# Filtro_8vo_Orden.net
KiCad netlist of a schematic drawn in EAGLE
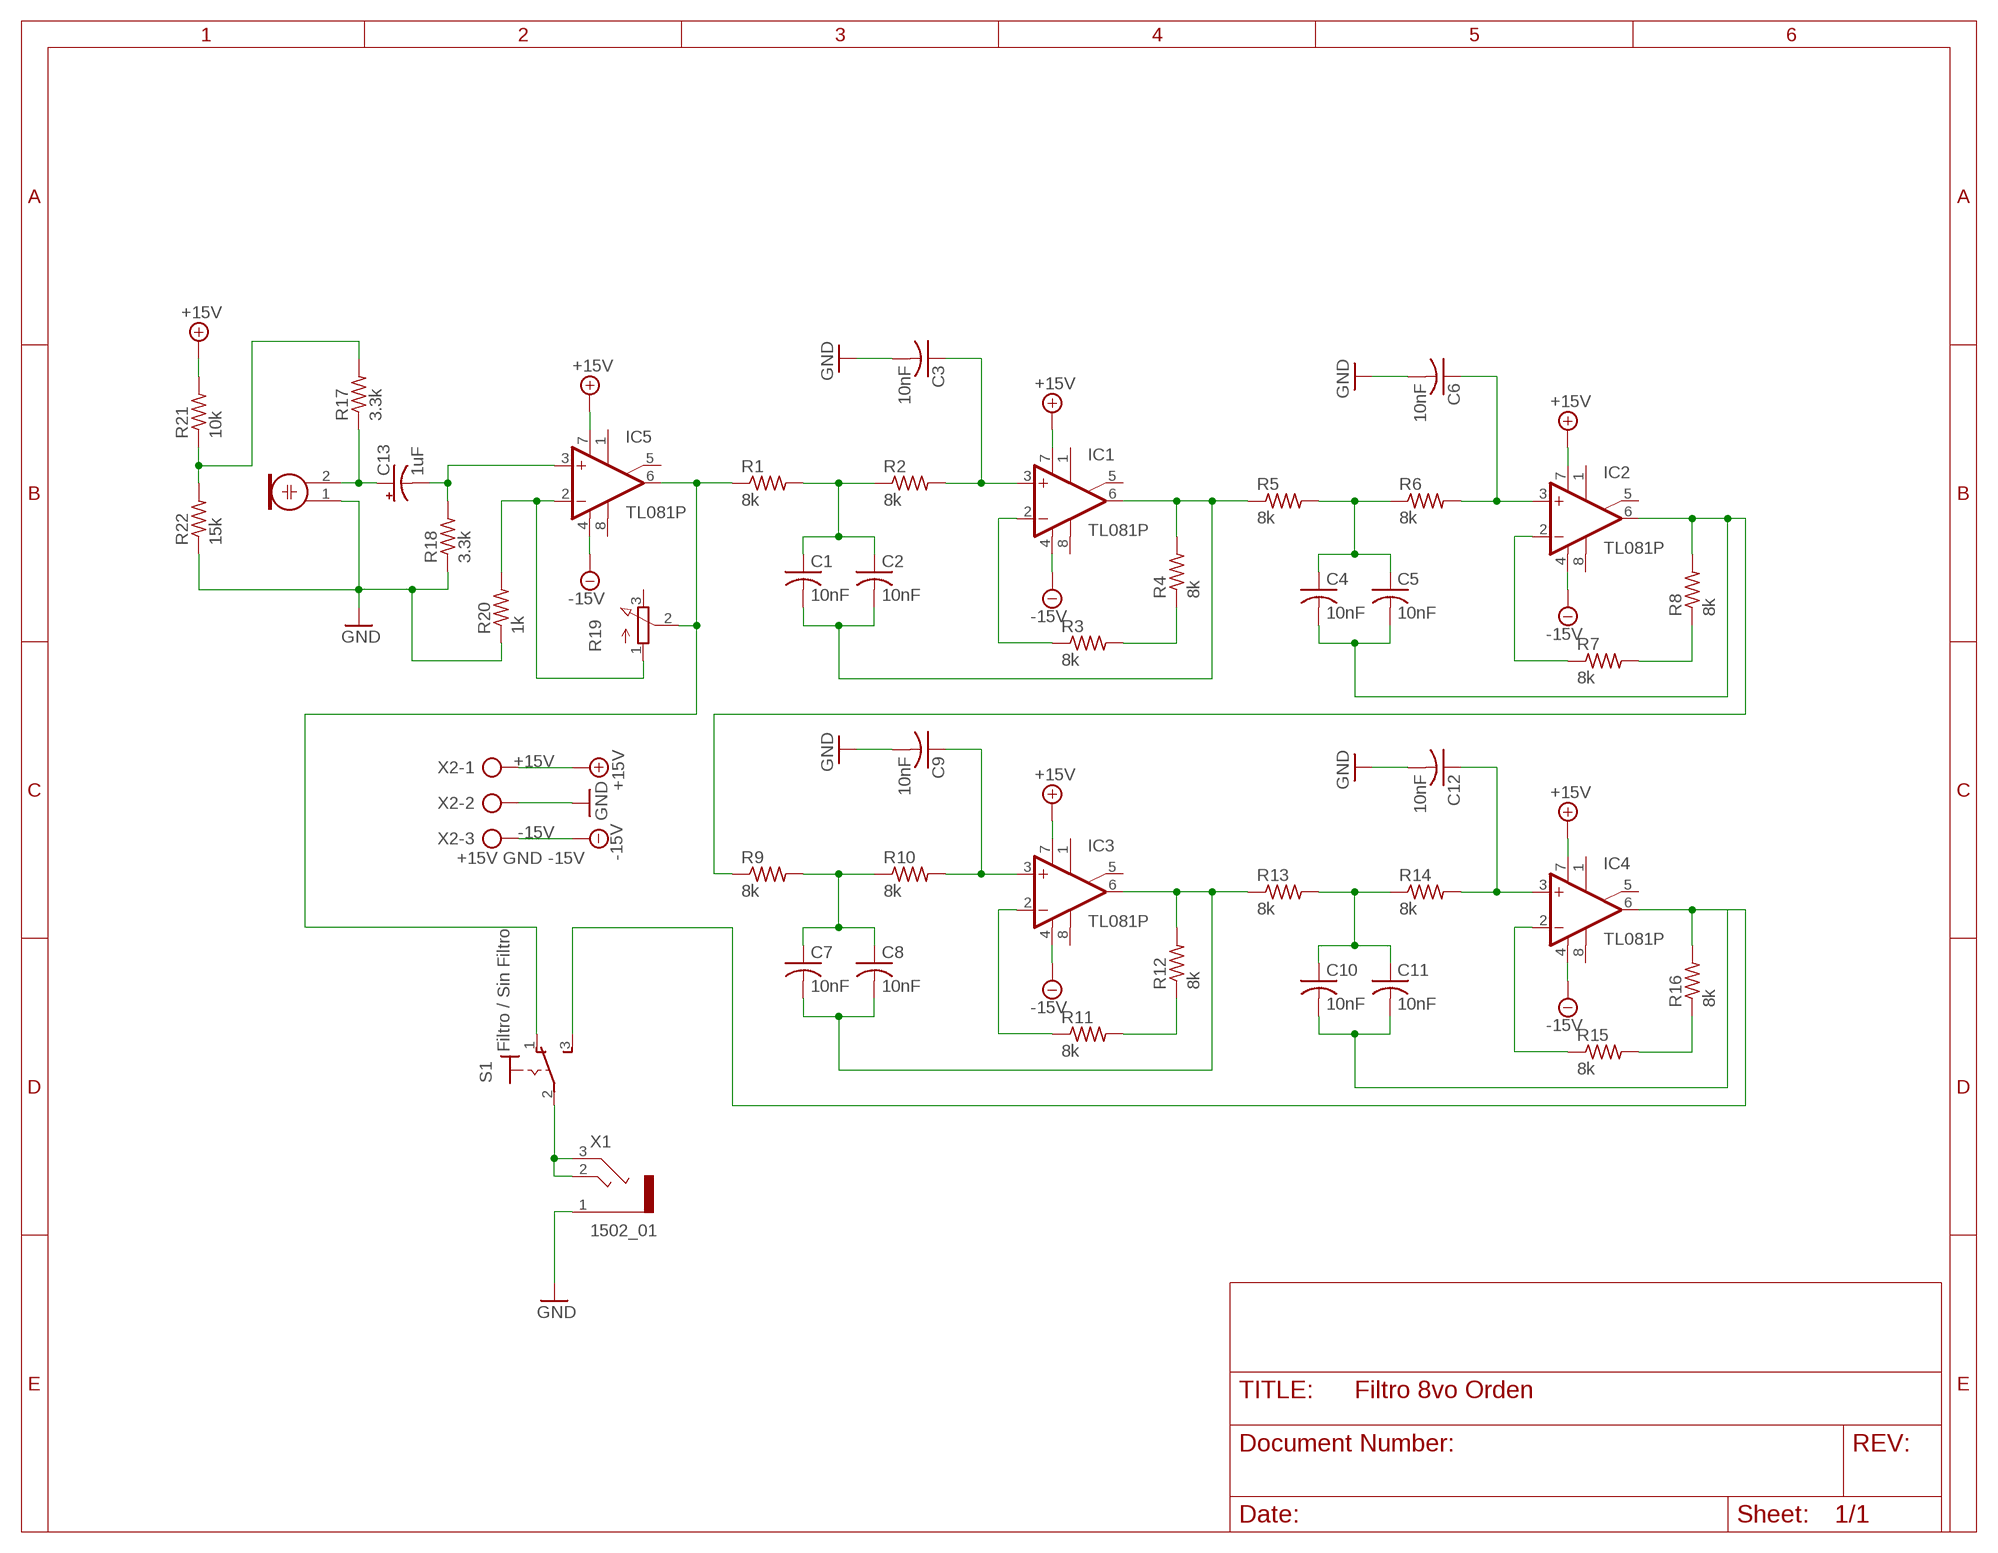
[diagram p0: schematic, sheet 1]

(export (version "E")
  (design (tool "Eeschema 10.0.6"))
  (components
    (comp (ref "C1")
      (value "10nF")
      (footprint "eagle-import:C0805")
      (libsource (lib "eagle-import") (part "C-USC0805"))
    )
    (comp (ref "C2")
      (value "10nF")
      (footprint "eagle-import:C0805")
      (libsource (lib "eagle-import") (part "C-USC0805"))
    )
    (comp (ref "C3")
      (value "10nF")
      (footprint "eagle-import:C0805")
      (libsource (lib "eagle-import") (part "C-USC0805"))
    )
    (comp (ref "C4")
      (value "10nF")
      (footprint "eagle-import:C0805")
      (libsource (lib "eagle-import") (part "C-USC0805"))
    )
    (comp (ref "C5")
      (value "10nF")
      (footprint "eagle-import:C0805")
      (libsource (lib "eagle-import") (part "C-USC0805"))
    )
    (comp (ref "C6")
      (value "10nF")
      (footprint "eagle-import:C0805")
      (libsource (lib "eagle-import") (part "C-USC0805"))
    )
    (comp (ref "C7")
      (value "10nF")
      (footprint "eagle-import:C0805")
      (libsource (lib "eagle-import") (part "C-USC0805"))
    )
    (comp (ref "C8")
      (value "10nF")
      (footprint "eagle-import:C0805")
      (libsource (lib "eagle-import") (part "C-USC0805"))
    )
    (comp (ref "C9")
      (value "10nF")
      (footprint "eagle-import:C0805")
      (libsource (lib "eagle-import") (part "C-USC0805"))
    )
    (comp (ref "C10")
      (value "10nF")
      (footprint "eagle-import:C0805")
      (libsource (lib "eagle-import") (part "C-USC0805"))
    )
    (comp (ref "C11")
      (value "10nF")
      (footprint "eagle-import:C0805")
      (libsource (lib "eagle-import") (part "C-USC0805"))
    )
    (comp (ref "C12")
      (value "10nF")
      (footprint "eagle-import:C0805")
      (libsource (lib "eagle-import") (part "C-USC0805"))
    )
    (comp (ref "C13")
      (value "1uF")
      (footprint "eagle-import:E1,8-4")
      (libsource (lib "eagle-import") (part "CPOL-USE1.8-4"))
    )
    (comp (ref "IC1")
      (value "TL081P")
      (footprint "eagle-import:DIL08")
      (libsource (lib "eagle-import") (part "TL081P"))
    )
    (comp (ref "IC2")
      (value "TL081P")
      (footprint "eagle-import:DIL08")
      (libsource (lib "eagle-import") (part "TL081P"))
    )
    (comp (ref "IC3")
      (value "TL081P")
      (footprint "eagle-import:DIL08")
      (libsource (lib "eagle-import") (part "TL081P"))
    )
    (comp (ref "IC4")
      (value "TL081P")
      (footprint "eagle-import:DIL08")
      (libsource (lib "eagle-import") (part "TL081P"))
    )
    (comp (ref "IC5")
      (value "TL081P")
      (footprint "eagle-import:DIL08")
      (libsource (lib "eagle-import") (part "TL081P"))
    )
    (comp (ref "M1")
      (value "ELECTRET_MICROPHONWM-63PR")
      (footprint "eagle-import:WM-63PR")
      (libsource (lib "eagle-import") (part "ELECTRET_MICROPHONWM-63PR"))
    )
    (comp (ref "R1")
      (value "8k")
      (footprint "eagle-import:0204_7")
      (libsource (lib "eagle-import") (part "R-US_0204/7"))
    )
    (comp (ref "R2")
      (value "8k")
      (footprint "eagle-import:0204_7")
      (libsource (lib "eagle-import") (part "R-US_0204/7"))
    )
    (comp (ref "R3")
      (value "8k")
      (footprint "eagle-import:0204_7")
      (libsource (lib "eagle-import") (part "R-US_0204/7"))
    )
    (comp (ref "R4")
      (value "8k")
      (footprint "eagle-import:0204_7")
      (libsource (lib "eagle-import") (part "R-US_0204/7"))
    )
    (comp (ref "R5")
      (value "8k")
      (footprint "eagle-import:0204_7")
      (libsource (lib "eagle-import") (part "R-US_0204/7"))
    )
    (comp (ref "R6")
      (value "8k")
      (footprint "eagle-import:0204_7")
      (libsource (lib "eagle-import") (part "R-US_0204/7"))
    )
    (comp (ref "R7")
      (value "8k")
      (footprint "eagle-import:0204_7")
      (libsource (lib "eagle-import") (part "R-US_0204/7"))
    )
    (comp (ref "R8")
      (value "8k")
      (footprint "eagle-import:0204_7")
      (libsource (lib "eagle-import") (part "R-US_0204/7"))
    )
    (comp (ref "R9")
      (value "8k")
      (footprint "eagle-import:0204_7")
      (libsource (lib "eagle-import") (part "R-US_0204/7"))
    )
    (comp (ref "R10")
      (value "8k")
      (footprint "eagle-import:0204_7")
      (libsource (lib "eagle-import") (part "R-US_0204/7"))
    )
    (comp (ref "R11")
      (value "8k")
      (footprint "eagle-import:0204_7")
      (libsource (lib "eagle-import") (part "R-US_0204/7"))
    )
    (comp (ref "R12")
      (value "8k")
      (footprint "eagle-import:0204_7")
      (libsource (lib "eagle-import") (part "R-US_0204/7"))
    )
    (comp (ref "R13")
      (value "8k")
      (footprint "eagle-import:0204_7")
      (libsource (lib "eagle-import") (part "R-US_0204/7"))
    )
    (comp (ref "R14")
      (value "8k")
      (footprint "eagle-import:0204_7")
      (libsource (lib "eagle-import") (part "R-US_0204/7"))
    )
    (comp (ref "R15")
      (value "8k")
      (footprint "eagle-import:0204_7")
      (libsource (lib "eagle-import") (part "R-US_0204/7"))
    )
    (comp (ref "R16")
      (value "8k")
      (footprint "eagle-import:0204_7")
      (libsource (lib "eagle-import") (part "R-US_0204/7"))
    )
    (comp (ref "R17")
      (value "3.3k")
      (footprint "eagle-import:0204_7")
      (libsource (lib "eagle-import") (part "R-US_0204/7"))
    )
    (comp (ref "R18")
      (value "3.3k")
      (footprint "eagle-import:0204_7")
      (libsource (lib "eagle-import") (part "R-US_0204/7"))
    )
    (comp (ref "R19")
      (value "3RP/1610N")
      (footprint "eagle-import:3RP_1610N")
      (libsource (lib "eagle-import") (part "3RP/1610N"))
    )
    (comp (ref "R20")
      (value "1k")
      (footprint "eagle-import:0204_7")
      (libsource (lib "eagle-import") (part "R-US_0204/7"))
    )
    (comp (ref "R21")
      (value "10k")
      (footprint "eagle-import:0204_7")
      (libsource (lib "eagle-import") (part "R-US_0204/7"))
    )
    (comp (ref "R22")
      (value "15k")
      (footprint "eagle-import:0204_7")
      (libsource (lib "eagle-import") (part "R-US_0204/7"))
    )
    (comp (ref "S1")
      (value "Filtro / Sin Filtro")
      (footprint "eagle-import:320-916")
      (libsource (lib "eagle-import") (part "320-916"))
    )
    (comp (ref "X1")
      (value "1502_01")
      (footprint "eagle-import:1502_01")
      (libsource (lib "eagle-import") (part "1502_01"))
    )
    (comp (ref "X2")
      (value "+15V GND -15V")
      (footprint "eagle-import:AK300_3")
      (libsource (lib "eagle-import") (part "AK300/3"))
    )
  )
  (nets
    (net (code "1") (name "+15V") (class "Default")
      (node (ref "IC1") (pin "7") (pinfunction "V+_7") (pintype "power_in"))
      (node (ref "IC2") (pin "7") (pinfunction "V+_7") (pintype "power_in"))
      (node (ref "IC3") (pin "7") (pinfunction "V+_7") (pintype "power_in"))
      (node (ref "IC4") (pin "7") (pinfunction "V+_7") (pintype "power_in"))
      (node (ref "IC5") (pin "7") (pinfunction "V+_7") (pintype "power_in"))
      (node (ref "R21") (pin "2") (pinfunction "2_2") (pintype "passive"))
      (node (ref "X2") (pin "1") (pinfunction "KL_1") (pintype "passive"))
    )
    (net (code "2") (name "-15V") (class "Default")
      (node (ref "IC1") (pin "4") (pinfunction "V-_4") (pintype "power_in"))
      (node (ref "IC2") (pin "4") (pinfunction "V-_4") (pintype "power_in"))
      (node (ref "IC3") (pin "4") (pinfunction "V-_4") (pintype "power_in"))
      (node (ref "IC4") (pin "4") (pinfunction "V-_4") (pintype "power_in"))
      (node (ref "IC5") (pin "4") (pinfunction "V-_4") (pintype "power_in"))
      (node (ref "X2") (pin "3") (pinfunction "KL_3") (pintype "passive"))
    )
    (net (code "3") (name "GND") (class "Default")
      (node (ref "C12") (pin "2") (pinfunction "2_2") (pintype "passive"))
      (node (ref "C3") (pin "2") (pinfunction "2_2") (pintype "passive"))
      (node (ref "C6") (pin "2") (pinfunction "2_2") (pintype "passive"))
      (node (ref "C9") (pin "2") (pinfunction "2_2") (pintype "passive"))
      (node (ref "M1") (pin "1") (pinfunction "1_1") (pintype "passive"))
      (node (ref "R18") (pin "1") (pinfunction "1_1") (pintype "passive"))
      (node (ref "R20") (pin "1") (pinfunction "1_1") (pintype "passive"))
      (node (ref "R22") (pin "1") (pinfunction "1_1") (pintype "passive"))
      (node (ref "X1") (pin "1") (pinfunction "1_1") (pintype "passive"))
      (node (ref "X2") (pin "2") (pinfunction "KL_2") (pintype "passive"))
    )
    (net (code "4") (name "Net-(C1-Pad1)") (class "Default")
      (node (ref "C1") (pin "1") (pinfunction "1_1") (pintype "passive"))
      (node (ref "C2") (pin "1") (pinfunction "1_1") (pintype "passive"))
      (node (ref "R1") (pin "2") (pinfunction "2_2") (pintype "passive"))
      (node (ref "R2") (pin "1") (pinfunction "1_1") (pintype "passive"))
    )
    (net (code "5") (name "Net-(C4-Pad1)") (class "Default")
      (node (ref "C4") (pin "1") (pinfunction "1_1") (pintype "passive"))
      (node (ref "C5") (pin "1") (pinfunction "1_1") (pintype "passive"))
      (node (ref "R5") (pin "2") (pinfunction "2_2") (pintype "passive"))
      (node (ref "R6") (pin "1") (pinfunction "1_1") (pintype "passive"))
    )
    (net (code "6") (name "Net-(C7-Pad1)") (class "Default")
      (node (ref "C7") (pin "1") (pinfunction "1_1") (pintype "passive"))
      (node (ref "C8") (pin "1") (pinfunction "1_1") (pintype "passive"))
      (node (ref "R10") (pin "1") (pinfunction "1_1") (pintype "passive"))
      (node (ref "R9") (pin "2") (pinfunction "2_2") (pintype "passive"))
    )
    (net (code "7") (name "Net-(C10-Pad1)") (class "Default")
      (node (ref "C10") (pin "1") (pinfunction "1_1") (pintype "passive"))
      (node (ref "C11") (pin "1") (pinfunction "1_1") (pintype "passive"))
      (node (ref "R13") (pin "2") (pinfunction "2_2") (pintype "passive"))
      (node (ref "R14") (pin "1") (pinfunction "1_1") (pintype "passive"))
    )
    (net (code "8") (name "Net-(C13-Pad+)") (class "Default")
      (node (ref "C13") (pin "+") (pinfunction "+_+") (pintype "passive"))
      (node (ref "M1") (pin "2") (pinfunction "2_2") (pintype "passive"))
      (node (ref "R17") (pin "1") (pinfunction "1_1") (pintype "passive"))
    )
    (net (code "9") (name "Net-(IC1-+IN)") (class "Default")
      (node (ref "C3") (pin "1") (pinfunction "1_1") (pintype "passive"))
      (node (ref "IC1") (pin "3") (pinfunction "+IN_3") (pintype "input"))
      (node (ref "R2") (pin "2") (pinfunction "2_2") (pintype "passive"))
    )
    (net (code "10") (name "Net-(IC1--IN)") (class "Default")
      (node (ref "IC1") (pin "2") (pinfunction "-IN_2") (pintype "input"))
      (node (ref "R3") (pin "1") (pinfunction "1_1") (pintype "passive"))
    )
    (net (code "11") (name "Net-(IC1-OUT)") (class "Default")
      (node (ref "C1") (pin "2") (pinfunction "2_2") (pintype "passive"))
      (node (ref "C2") (pin "2") (pinfunction "2_2") (pintype "passive"))
      (node (ref "IC1") (pin "6") (pinfunction "OUT_6") (pintype "output"))
      (node (ref "R4") (pin "2") (pinfunction "2_2") (pintype "passive"))
      (node (ref "R5") (pin "1") (pinfunction "1_1") (pintype "passive"))
    )
    (net (code "12") (name "Net-(IC2-+IN)") (class "Default")
      (node (ref "C6") (pin "1") (pinfunction "1_1") (pintype "passive"))
      (node (ref "IC2") (pin "3") (pinfunction "+IN_3") (pintype "input"))
      (node (ref "R6") (pin "2") (pinfunction "2_2") (pintype "passive"))
    )
    (net (code "13") (name "Net-(IC2--IN)") (class "Default")
      (node (ref "IC2") (pin "2") (pinfunction "-IN_2") (pintype "input"))
      (node (ref "R7") (pin "1") (pinfunction "1_1") (pintype "passive"))
    )
    (net (code "14") (name "Net-(IC2-OUT)") (class "Default")
      (node (ref "C4") (pin "2") (pinfunction "2_2") (pintype "passive"))
      (node (ref "C5") (pin "2") (pinfunction "2_2") (pintype "passive"))
      (node (ref "IC2") (pin "6") (pinfunction "OUT_6") (pintype "output"))
      (node (ref "R8") (pin "2") (pinfunction "2_2") (pintype "passive"))
      (node (ref "R9") (pin "1") (pinfunction "1_1") (pintype "passive"))
    )
    (net (code "15") (name "Net-(IC3-+IN)") (class "Default")
      (node (ref "C9") (pin "1") (pinfunction "1_1") (pintype "passive"))
      (node (ref "IC3") (pin "3") (pinfunction "+IN_3") (pintype "input"))
      (node (ref "R10") (pin "2") (pinfunction "2_2") (pintype "passive"))
    )
    (net (code "16") (name "Net-(IC3--IN)") (class "Default")
      (node (ref "IC3") (pin "2") (pinfunction "-IN_2") (pintype "input"))
      (node (ref "R11") (pin "1") (pinfunction "1_1") (pintype "passive"))
    )
    (net (code "17") (name "Net-(IC3-OUT)") (class "Default")
      (node (ref "C7") (pin "2") (pinfunction "2_2") (pintype "passive"))
      (node (ref "C8") (pin "2") (pinfunction "2_2") (pintype "passive"))
      (node (ref "IC3") (pin "6") (pinfunction "OUT_6") (pintype "output"))
      (node (ref "R12") (pin "2") (pinfunction "2_2") (pintype "passive"))
      (node (ref "R13") (pin "1") (pinfunction "1_1") (pintype "passive"))
    )
    (net (code "18") (name "Net-(IC4-+IN)") (class "Default")
      (node (ref "C12") (pin "1") (pinfunction "1_1") (pintype "passive"))
      (node (ref "IC4") (pin "3") (pinfunction "+IN_3") (pintype "input"))
      (node (ref "R14") (pin "2") (pinfunction "2_2") (pintype "passive"))
    )
    (net (code "19") (name "Net-(IC4--IN)") (class "Default")
      (node (ref "IC4") (pin "2") (pinfunction "-IN_2") (pintype "input"))
      (node (ref "R15") (pin "1") (pinfunction "1_1") (pintype "passive"))
    )
    (net (code "20") (name "Net-(IC4-OUT)") (class "Default")
      (node (ref "C10") (pin "2") (pinfunction "2_2") (pintype "passive"))
      (node (ref "C11") (pin "2") (pinfunction "2_2") (pintype "passive"))
      (node (ref "IC4") (pin "6") (pinfunction "OUT_6") (pintype "output"))
      (node (ref "R16") (pin "2") (pinfunction "2_2") (pintype "passive"))
      (node (ref "S1") (pin "3") (pinfunction "S_3") (pintype "passive"))
    )
    (net (code "21") (name "Net-(IC5-+IN)") (class "Default")
      (node (ref "C13") (pin "-") (pinfunction "-_-") (pintype "passive"))
      (node (ref "IC5") (pin "3") (pinfunction "+IN_3") (pintype "input"))
      (node (ref "R18") (pin "2") (pinfunction "2_2") (pintype "passive"))
    )
    (net (code "22") (name "Net-(IC5--IN)") (class "Default")
      (node (ref "IC5") (pin "2") (pinfunction "-IN_2") (pintype "input"))
      (node (ref "R19") (pin "1") (pinfunction "A_1") (pintype "passive"))
      (node (ref "R20") (pin "2") (pinfunction "2_2") (pintype "passive"))
    )
    (net (code "23") (name "Net-(IC5-OUT)") (class "Default")
      (node (ref "IC5") (pin "6") (pinfunction "OUT_6") (pintype "output"))
      (node (ref "R1") (pin "1") (pinfunction "1_1") (pintype "passive"))
      (node (ref "R19") (pin "2") (pinfunction "S_2") (pintype "passive"))
      (node (ref "S1") (pin "1") (pinfunction "O_1") (pintype "passive"))
    )
    (net (code "24") (name "Net-(R3-Pad2)") (class "Default")
      (node (ref "R3") (pin "2") (pinfunction "2_2") (pintype "passive"))
      (node (ref "R4") (pin "1") (pinfunction "1_1") (pintype "passive"))
    )
    (net (code "25") (name "Net-(R7-Pad2)") (class "Default")
      (node (ref "R7") (pin "2") (pinfunction "2_2") (pintype "passive"))
      (node (ref "R8") (pin "1") (pinfunction "1_1") (pintype "passive"))
    )
    (net (code "26") (name "Net-(R11-Pad2)") (class "Default")
      (node (ref "R11") (pin "2") (pinfunction "2_2") (pintype "passive"))
      (node (ref "R12") (pin "1") (pinfunction "1_1") (pintype "passive"))
    )
    (net (code "27") (name "Net-(R15-Pad2)") (class "Default")
      (node (ref "R15") (pin "2") (pinfunction "2_2") (pintype "passive"))
      (node (ref "R16") (pin "1") (pinfunction "1_1") (pintype "passive"))
    )
    (net (code "28") (name "Net-(R17-Pad2)") (class "Default")
      (node (ref "R17") (pin "2") (pinfunction "2_2") (pintype "passive"))
      (node (ref "R21") (pin "1") (pinfunction "1_1") (pintype "passive"))
      (node (ref "R22") (pin "2") (pinfunction "2_2") (pintype "passive"))
    )
    (net (code "29") (name "Net-(S1-P)") (class "Default")
      (node (ref "S1") (pin "2") (pinfunction "P_2") (pintype "passive"))
      (node (ref "X1") (pin "2") (pinfunction "3_2") (pintype "passive"))
      (node (ref "X1") (pin "3") (pinfunction "2_3") (pintype "passive"))
    )
    (net (code "30") (name "unconnected-(IC1-ON1-Pad1)") (class "Default")
      (node (ref "IC1") (pin "1") (pinfunction "ON1_1") (pintype "passive"))
    )
    (net (code "31") (name "unconnected-(IC1-ON2-Pad5)") (class "Default")
      (node (ref "IC1") (pin "5") (pinfunction "ON2_5") (pintype "passive"))
    )
    (net (code "32") (name "unconnected-(IC1-OPT-Pad8)") (class "Default")
      (node (ref "IC1") (pin "8") (pinfunction "OPT_8") (pintype "passive"))
    )
    (net (code "33") (name "unconnected-(IC2-ON1-Pad1)") (class "Default")
      (node (ref "IC2") (pin "1") (pinfunction "ON1_1") (pintype "passive"))
    )
    (net (code "34") (name "unconnected-(IC2-ON2-Pad5)") (class "Default")
      (node (ref "IC2") (pin "5") (pinfunction "ON2_5") (pintype "passive"))
    )
    (net (code "35") (name "unconnected-(IC2-OPT-Pad8)") (class "Default")
      (node (ref "IC2") (pin "8") (pinfunction "OPT_8") (pintype "passive"))
    )
    (net (code "36") (name "unconnected-(IC3-ON1-Pad1)") (class "Default")
      (node (ref "IC3") (pin "1") (pinfunction "ON1_1") (pintype "passive"))
    )
    (net (code "37") (name "unconnected-(IC3-ON2-Pad5)") (class "Default")
      (node (ref "IC3") (pin "5") (pinfunction "ON2_5") (pintype "passive"))
    )
    (net (code "38") (name "unconnected-(IC3-OPT-Pad8)") (class "Default")
      (node (ref "IC3") (pin "8") (pinfunction "OPT_8") (pintype "passive"))
    )
    (net (code "39") (name "unconnected-(IC4-ON1-Pad1)") (class "Default")
      (node (ref "IC4") (pin "1") (pinfunction "ON1_1") (pintype "passive"))
    )
    (net (code "40") (name "unconnected-(IC4-ON2-Pad5)") (class "Default")
      (node (ref "IC4") (pin "5") (pinfunction "ON2_5") (pintype "passive"))
    )
    (net (code "41") (name "unconnected-(IC4-OPT-Pad8)") (class "Default")
      (node (ref "IC4") (pin "8") (pinfunction "OPT_8") (pintype "passive"))
    )
    (net (code "42") (name "unconnected-(IC5-ON1-Pad1)") (class "Default")
      (node (ref "IC5") (pin "1") (pinfunction "ON1_1") (pintype "passive"))
    )
    (net (code "43") (name "unconnected-(IC5-ON2-Pad5)") (class "Default")
      (node (ref "IC5") (pin "5") (pinfunction "ON2_5") (pintype "passive"))
    )
    (net (code "44") (name "unconnected-(IC5-OPT-Pad8)") (class "Default")
      (node (ref "IC5") (pin "8") (pinfunction "OPT_8") (pintype "passive"))
    )
    (net (code "45") (name "unconnected-(R19-E-Pad3)") (class "Default")
      (node (ref "R19") (pin "3") (pinfunction "E_3") (pintype "passive"))
    )
  )
)
